# SCH_DART-Flight-Computer-5_2024-08-18.net
KiCad netlist of a schematic drawn in EasyEDA
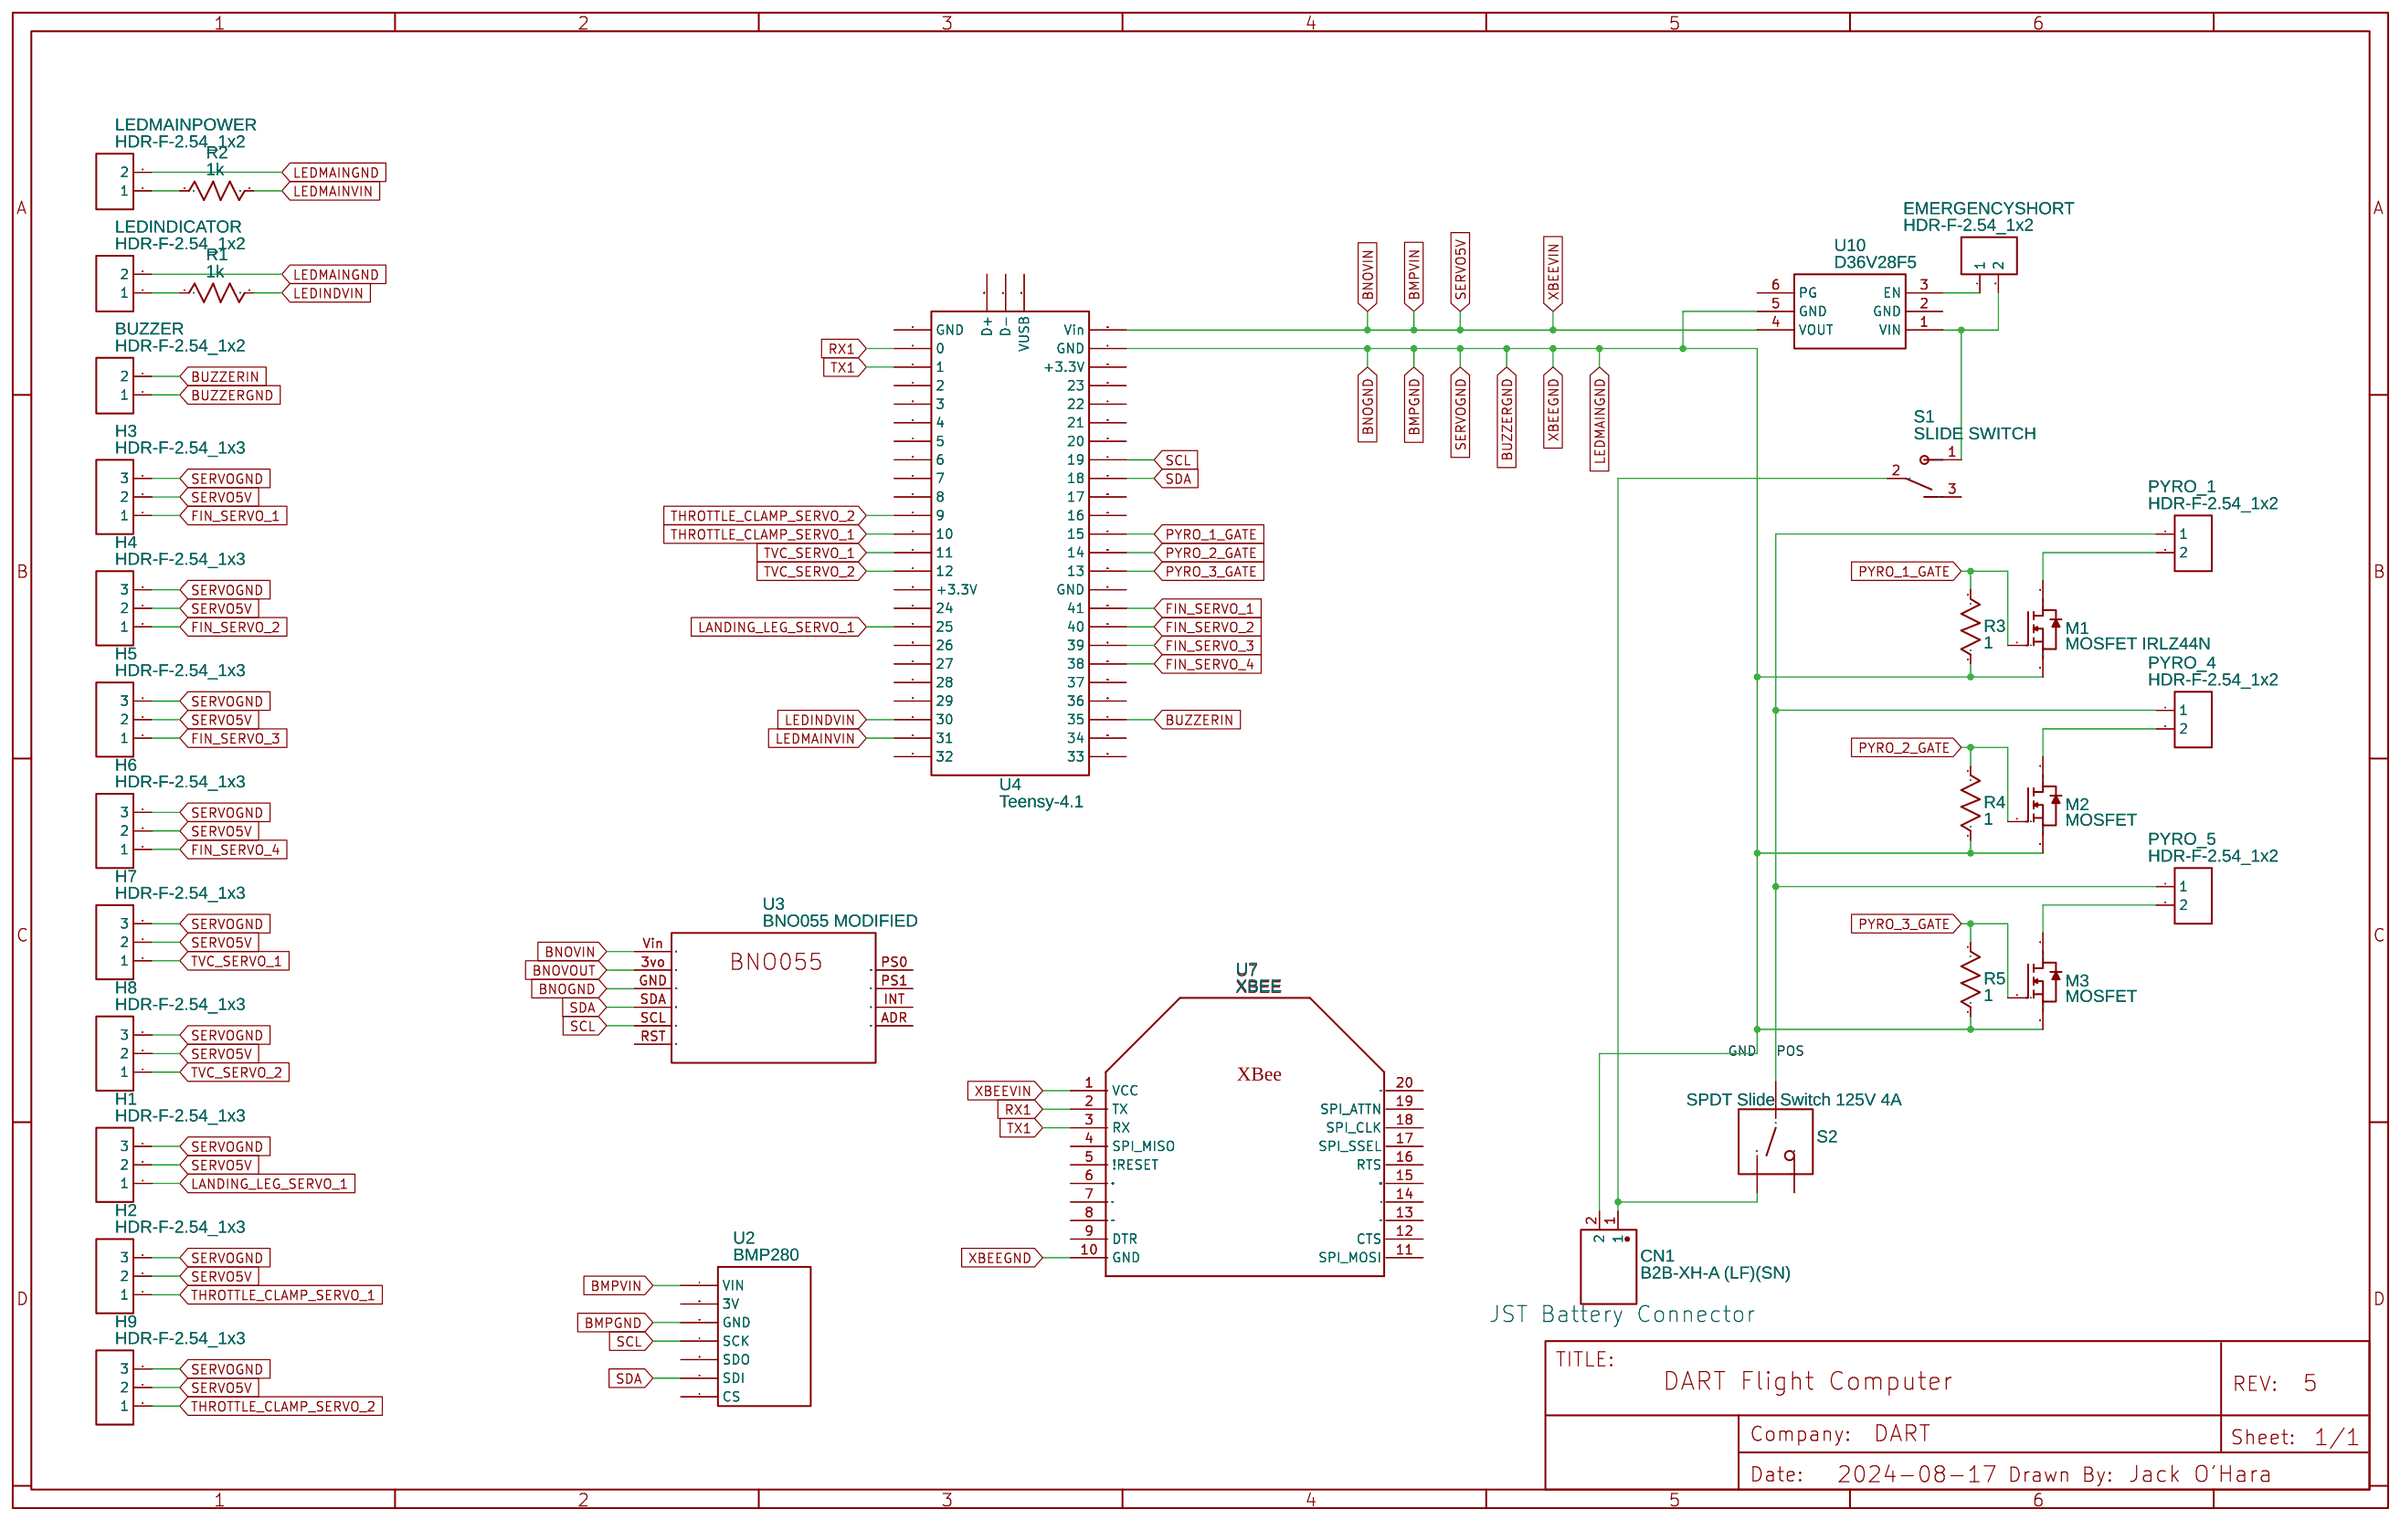
[diagram p0: schematic sheet]

(export (version "E")
  (design (tool "Eeschema 10.0.6"))
  (components
    (comp (ref "BUZZER") (value "HDR-F-2.54_1x2") (libsource (lib "") (part "HDR-F-2.54_1x2_4")))
    (comp (ref "CN1")
      (value "B2B-XH-A (LF)(SN)")
      (fields (field (name "Manufacturer Part") "B2B-XH-A(LF)(SN)") (field (name "Manufacturer") "JST"))
      (libsource (lib "") (part "B2B-XH-A (LF)(SN)"))
    )
    (comp (ref "EMERGENCYSHORT") (value "HDR-F-2.54_1x2") (libsource (lib "") (part "HDR-F-2.54_1x2_2")))
    (comp (ref "H1") (value "HDR-F-2.54_1x3") (libsource (lib "") (part "HDR-F-2.54_1x3")))
    (comp (ref "H2") (value "HDR-F-2.54_1x3") (libsource (lib "") (part "HDR-F-2.54_1x3")))
    (comp (ref "H3") (value "HDR-F-2.54_1x3") (libsource (lib "") (part "HDR-F-2.54_1x3")))
    (comp (ref "H4") (value "HDR-F-2.54_1x3") (libsource (lib "") (part "HDR-F-2.54_1x3")))
    (comp (ref "H5") (value "HDR-F-2.54_1x3") (libsource (lib "") (part "HDR-F-2.54_1x3")))
    (comp (ref "H6") (value "HDR-F-2.54_1x3") (libsource (lib "") (part "HDR-F-2.54_1x3")))
    (comp (ref "H7") (value "HDR-F-2.54_1x3") (libsource (lib "") (part "HDR-F-2.54_1x3")))
    (comp (ref "H8") (value "HDR-F-2.54_1x3") (libsource (lib "") (part "HDR-F-2.54_1x3")))
    (comp (ref "H9") (value "HDR-F-2.54_1x3") (libsource (lib "") (part "HDR-F-2.54_1x3")))
    (comp (ref "LEDINDICATOR") (value "HDR-F-2.54_1x2") (libsource (lib "") (part "HDR-F-2.54_1x2_3")))
    (comp (ref "LEDMAINPOWER") (value "HDR-F-2.54_1x2") (libsource (lib "") (part "HDR-F-2.54_1x2")))
    (comp (ref "M1") (value "MOSFET IRLZ44N") (libsource (lib "") (part "MOSFET")))
    (comp (ref "M2") (value "MOSFET") (libsource (lib "") (part "MOSFET")))
    (comp (ref "M3") (value "MOSFET") (libsource (lib "") (part "MOSFET")))
    (comp (ref "PYRO_1") (value "HDR-F-2.54_1x2") (libsource (lib "") (part "HDR-F-2.54_1x2_1")))
    (comp (ref "PYRO_4") (value "HDR-F-2.54_1x2") (libsource (lib "") (part "HDR-F-2.54_1x2_1")))
    (comp (ref "PYRO_5") (value "HDR-F-2.54_1x2") (libsource (lib "") (part "HDR-F-2.54_1x2_1")))
    (comp (ref "R1") (value "1k") (libsource (lib "") (part "R_0603_US")))
    (comp (ref "R2") (value "1k") (libsource (lib "") (part "R_0603_US")))
    (comp (ref "R3") (value "1") (libsource (lib "") (part "R_0603_US_1")))
    (comp (ref "R4") (value "1") (libsource (lib "") (part "R_0603_US_1")))
    (comp (ref "R5") (value "1") (libsource (lib "") (part "R_0603_US_1")))
    (comp (ref "S1") (value "SLIDE SWITCH") (libsource (lib "") (part "SLIDE SWITCH")))
    (comp (ref "S2")
      (value "SPDT Slide Switch 125V 4A")
      (fields
        (field (name "Manufacturer Part") "8SS1012-Z")
        (field (name "Manufacturer") "Nidec Copal Electronics")
      )
      (libsource (lib "") (part "SPDT Slide Switch 125V 4A"))
    )
    (comp (ref "U2") (value "BMP280") (libsource (lib "") (part "BMP280")))
    (comp (ref "U3") (value "BNO055 MODIFIED") (libsource (lib "") (part "BNO055 MODIFIED")))
    (comp (ref "U4") (value "Teensy-4.1") (libsource (lib "") (part "Teensy-4.1")))
    (comp (ref "U7") (value "XBEE") (libsource (lib "") (part "XBEE")))
    (comp (ref "U10")
      (value "D36V28F5")
      (fields
        (field (name "Manufacturer Part") "Pololu D36V28F5 Step-down regulator 5v fixed")
        (field (name "Manufacturer") "Pololu")
      )
      (libsource (lib "") (part "D36V28F5"))
    )
  )
  (nets
    (net (code "1") (name "/POS") (class "Default")
      (node (ref "PYRO_1") (pin "1") (pinfunction "1_1") (pintype "input"))
      (node (ref "PYRO_4") (pin "1") (pinfunction "1_1") (pintype "input"))
      (node (ref "PYRO_5") (pin "1") (pinfunction "1_1") (pintype "input"))
      (node (ref "S2") (pin "2") (pinfunction "2_2") (pintype "unspecified"))
    )
    (net (code "2") (name "BMPGND") (class "Default")
      (node (ref "BUZZER") (pin "1") (pinfunction "1_1") (pintype "input"))
      (node (ref "CN1") (pin "2") (pinfunction "2_2") (pintype "unspecified"))
      (node (ref "H1") (pin "3") (pinfunction "3_3") (pintype "input"))
      (node (ref "H2") (pin "3") (pinfunction "3_3") (pintype "input"))
      (node (ref "H3") (pin "3") (pinfunction "3_3") (pintype "input"))
      (node (ref "H4") (pin "3") (pinfunction "3_3") (pintype "input"))
      (node (ref "H5") (pin "3") (pinfunction "3_3") (pintype "input"))
      (node (ref "H6") (pin "3") (pinfunction "3_3") (pintype "input"))
      (node (ref "H7") (pin "3") (pinfunction "3_3") (pintype "input"))
      (node (ref "H8") (pin "3") (pinfunction "3_3") (pintype "input"))
      (node (ref "H9") (pin "3") (pinfunction "3_3") (pintype "input"))
      (node (ref "LEDINDICATOR") (pin "2") (pinfunction "2_2") (pintype "input"))
      (node (ref "LEDMAINPOWER") (pin "2") (pinfunction "2_2") (pintype "input"))
      (node (ref "M1") (pin "2") (pinfunction "2_2") (pintype "unspecified"))
      (node (ref "M2") (pin "2") (pinfunction "2_2") (pintype "unspecified"))
      (node (ref "M3") (pin "2") (pinfunction "2_2") (pintype "unspecified"))
      (node (ref "R3") (pin "1") (pinfunction "1_1") (pintype "unspecified"))
      (node (ref "R4") (pin "1") (pinfunction "1_1") (pintype "unspecified"))
      (node (ref "R5") (pin "1") (pinfunction "1_1") (pintype "unspecified"))
      (node (ref "U10") (pin "5") (pinfunction "GND_5") (pintype "unspecified"))
      (node (ref "U2") (pin "5") (pinfunction "GND_5") (pintype "unspecified"))
      (node (ref "U3") (pin "GND") (pinfunction "GND_GND") (pintype "unspecified"))
      (node (ref "U4") (pin "47") (pinfunction "GND_47") (pintype "unspecified"))
      (node (ref "U7") (pin "10") (pinfunction "GND_10") (pintype "unspecified"))
    )
    (net (code "3") (name "BMPVIN") (class "Default")
      (node (ref "H1") (pin "2") (pinfunction "2_2") (pintype "input"))
      (node (ref "H2") (pin "2") (pinfunction "2_2") (pintype "input"))
      (node (ref "H3") (pin "2") (pinfunction "2_2") (pintype "input"))
      (node (ref "H4") (pin "2") (pinfunction "2_2") (pintype "input"))
      (node (ref "H5") (pin "2") (pinfunction "2_2") (pintype "input"))
      (node (ref "H6") (pin "2") (pinfunction "2_2") (pintype "input"))
      (node (ref "H7") (pin "2") (pinfunction "2_2") (pintype "input"))
      (node (ref "H8") (pin "2") (pinfunction "2_2") (pintype "input"))
      (node (ref "H9") (pin "2") (pinfunction "2_2") (pintype "input"))
      (node (ref "U10") (pin "4") (pinfunction "VOUT_4") (pintype "unspecified"))
      (node (ref "U2") (pin "7") (pinfunction "VIN_7") (pintype "unspecified"))
      (node (ref "U3") (pin "Vin") (pinfunction "Vin_Vin") (pintype "unspecified"))
      (node (ref "U4") (pin "48") (pinfunction "Vin_48") (pintype "unspecified"))
      (node (ref "U7") (pin "1") (pinfunction "VCC_1") (pintype "unspecified"))
    )
    (net (code "4") (name "BNOVOUT") (class "Default")
      (node (ref "U3") (pin "3vo") (pinfunction "3vo_3vo") (pintype "unspecified"))
    )
    (net (code "5") (name "BUZZERIN") (class "Default")
      (node (ref "BUZZER") (pin "2") (pinfunction "2_2") (pintype "input"))
      (node (ref "U4") (pin "27") (pinfunction "35_27") (pintype "unspecified"))
    )
    (net (code "6") (name "FIN_SERVO_1") (class "Default")
      (node (ref "H3") (pin "1") (pinfunction "1_1") (pintype "input"))
      (node (ref "U4") (pin "33") (pinfunction "41_33") (pintype "unspecified"))
    )
    (net (code "7") (name "FIN_SERVO_2") (class "Default")
      (node (ref "H4") (pin "1") (pinfunction "1_1") (pintype "input"))
      (node (ref "U4") (pin "32") (pinfunction "40_32") (pintype "unspecified"))
    )
    (net (code "8") (name "FIN_SERVO_3") (class "Default")
      (node (ref "H5") (pin "1") (pinfunction "1_1") (pintype "input"))
      (node (ref "U4") (pin "31") (pinfunction "39_31") (pintype "unspecified"))
    )
    (net (code "9") (name "FIN_SERVO_4") (class "Default")
      (node (ref "H6") (pin "1") (pinfunction "1_1") (pintype "input"))
      (node (ref "U4") (pin "30") (pinfunction "38_30") (pintype "unspecified"))
    )
    (net (code "10") (name "LANDING_LEG_SERVO_1") (class "Default")
      (node (ref "H1") (pin "1") (pinfunction "1_1") (pintype "input"))
      (node (ref "U4") (pin "17") (pinfunction "25_17") (pintype "unspecified"))
    )
    (net (code "11") (name "LEDINDVIN") (class "Default")
      (node (ref "R1") (pin "2") (pinfunction "2_2") (pintype "unspecified"))
      (node (ref "U4") (pin "22") (pinfunction "30_22") (pintype "unspecified"))
    )
    (net (code "12") (name "LEDMAINVIN") (class "Default")
      (node (ref "R2") (pin "2") (pinfunction "2_2") (pintype "unspecified"))
      (node (ref "U4") (pin "23") (pinfunction "31_23") (pintype "unspecified"))
    )
    (net (code "13") (name "Net-(CN1-Pad1)") (class "Default")
      (node (ref "CN1") (pin "1") (pinfunction "1_1") (pintype "unspecified"))
      (node (ref "S1") (pin "2") (pinfunction "2_2") (pintype "bidirectional"))
      (node (ref "S2") (pin "3") (pinfunction "3_3") (pintype "unspecified"))
    )
    (net (code "14") (name "Net-(LEDINDICATOR-Pad1)") (class "Default")
      (node (ref "LEDINDICATOR") (pin "1") (pinfunction "1_1") (pintype "input"))
      (node (ref "R1") (pin "1") (pinfunction "1_1") (pintype "unspecified"))
    )
    (net (code "15") (name "Net-(LEDMAINPOWER-Pad1)") (class "Default")
      (node (ref "LEDMAINPOWER") (pin "1") (pinfunction "1_1") (pintype "input"))
      (node (ref "R2") (pin "1") (pinfunction "1_1") (pintype "unspecified"))
    )
    (net (code "16") (name "Net-(M1-Pad3)") (class "Default")
      (node (ref "M1") (pin "3") (pinfunction "3_3") (pintype "unspecified"))
      (node (ref "PYRO_1") (pin "2") (pinfunction "2_2") (pintype "input"))
    )
    (net (code "17") (name "Net-(M2-Pad3)") (class "Default")
      (node (ref "M2") (pin "3") (pinfunction "3_3") (pintype "unspecified"))
      (node (ref "PYRO_4") (pin "2") (pinfunction "2_2") (pintype "input"))
    )
    (net (code "18") (name "Net-(M3-Pad3)") (class "Default")
      (node (ref "M3") (pin "3") (pinfunction "3_3") (pintype "unspecified"))
      (node (ref "PYRO_5") (pin "2") (pinfunction "2_2") (pintype "input"))
    )
    (net (code "19") (name "Net-(U10-EN)") (class "Default")
      (node (ref "EMERGENCYSHORT") (pin "1") (pinfunction "1_1") (pintype "input"))
      (node (ref "U10") (pin "3") (pinfunction "EN_3") (pintype "unspecified"))
    )
    (net (code "20") (name "Net-(U10-VIN)") (class "Default")
      (node (ref "EMERGENCYSHORT") (pin "2") (pinfunction "2_2") (pintype "input"))
      (node (ref "S1") (pin "1") (pinfunction "1_1") (pintype "bidirectional"))
      (node (ref "U10") (pin "1") (pinfunction "VIN_1") (pintype "unspecified"))
    )
    (net (code "21") (name "PYRO_1_GATE") (class "Default")
      (node (ref "M1") (pin "1") (pinfunction "1_1") (pintype "unspecified"))
      (node (ref "R3") (pin "2") (pinfunction "2_2") (pintype "unspecified"))
      (node (ref "U4") (pin "37") (pinfunction "15_37") (pintype "unspecified"))
    )
    (net (code "22") (name "PYRO_2_GATE") (class "Default")
      (node (ref "M2") (pin "1") (pinfunction "1_1") (pintype "unspecified"))
      (node (ref "R4") (pin "2") (pinfunction "2_2") (pintype "unspecified"))
      (node (ref "U4") (pin "36") (pinfunction "14_36") (pintype "unspecified"))
    )
    (net (code "23") (name "PYRO_3_GATE") (class "Default")
      (node (ref "M3") (pin "1") (pinfunction "1_1") (pintype "unspecified"))
      (node (ref "R5") (pin "2") (pinfunction "2_2") (pintype "unspecified"))
      (node (ref "U4") (pin "35") (pinfunction "13_35") (pintype "unspecified"))
    )
    (net (code "24") (name "RX1") (class "Default")
      (node (ref "U4") (pin "2") (pinfunction "0_2") (pintype "unspecified"))
      (node (ref "U7") (pin "2") (pinfunction "TX_2") (pintype "output"))
    )
    (net (code "25") (name "SCL") (class "Default")
      (node (ref "U2") (pin "4") (pinfunction "SCK_4") (pintype "unspecified"))
      (node (ref "U3") (pin "SCL") (pinfunction "SCL_SCL") (pintype "unspecified"))
      (node (ref "U4") (pin "41") (pinfunction "19_41") (pintype "unspecified"))
    )
    (net (code "26") (name "SDA") (class "Default")
      (node (ref "U2") (pin "2") (pinfunction "SDI_2") (pintype "unspecified"))
      (node (ref "U3") (pin "SDA") (pinfunction "SDA_SDA") (pintype "unspecified"))
      (node (ref "U4") (pin "40") (pinfunction "18_40") (pintype "unspecified"))
    )
    (net (code "27") (name "THROTTLE_CLAMP_SERVO_1") (class "Default")
      (node (ref "H2") (pin "1") (pinfunction "1_1") (pintype "input"))
      (node (ref "U4") (pin "12") (pinfunction "10_12") (pintype "unspecified"))
    )
    (net (code "28") (name "THROTTLE_CLAMP_SERVO_2") (class "Default")
      (node (ref "H9") (pin "1") (pinfunction "1_1") (pintype "input"))
      (node (ref "U4") (pin "11") (pinfunction "9_11") (pintype "unspecified"))
    )
    (net (code "29") (name "TVC_SERVO_1") (class "Default")
      (node (ref "H7") (pin "1") (pinfunction "1_1") (pintype "input"))
      (node (ref "U4") (pin "13") (pinfunction "11_13") (pintype "unspecified"))
    )
    (net (code "30") (name "TVC_SERVO_2") (class "Default")
      (node (ref "H8") (pin "1") (pinfunction "1_1") (pintype "input"))
      (node (ref "U4") (pin "14") (pinfunction "12_14") (pintype "unspecified"))
    )
    (net (code "31") (name "TX1") (class "Default")
      (node (ref "U4") (pin "3") (pinfunction "1_3") (pintype "unspecified"))
      (node (ref "U7") (pin "3") (pinfunction "RX_3") (pintype "input"))
    )
    (net (code "32") (name "unconnected-(S1-Pad3)") (class "Default")
      (node (ref "S1") (pin "3") (pinfunction "3_3") (pintype "bidirectional"))
    )
    (net (code "33") (name "unconnected-(S2-Pad1)") (class "Default")
      (node (ref "S2") (pin "1") (pinfunction "1_1") (pintype "unspecified"))
    )
    (net (code "34") (name "unconnected-(U2-3V-Pad6)") (class "Default")
      (node (ref "U2") (pin "6") (pinfunction "3V_6") (pintype "unspecified"))
    )
    (net (code "35") (name "unconnected-(U2-CS-Pad1)") (class "Default")
      (node (ref "U2") (pin "1") (pinfunction "CS_1") (pintype "unspecified"))
    )
    (net (code "36") (name "unconnected-(U2-SDO-Pad3)") (class "Default")
      (node (ref "U2") (pin "3") (pinfunction "SDO_3") (pintype "unspecified"))
    )
    (net (code "37") (name "unconnected-(U3-PadADR)") (class "Default")
      (node (ref "U3") (pin "ADR") (pinfunction "ADR_ADR") (pintype "unspecified"))
    )
    (net (code "38") (name "unconnected-(U3-PadINT)") (class "Default")
      (node (ref "U3") (pin "INT") (pinfunction "INT_INT") (pintype "unspecified"))
    )
    (net (code "39") (name "unconnected-(U3-PadPS0)") (class "Default")
      (node (ref "U3") (pin "PS0") (pinfunction "PS0_PS0") (pintype "unspecified"))
    )
    (net (code "40") (name "unconnected-(U3-PadPS1)") (class "Default")
      (node (ref "U3") (pin "PS1") (pinfunction "PS1_PS1") (pintype "unspecified"))
    )
    (net (code "41") (name "unconnected-(U3-PadRST)") (class "Default")
      (node (ref "U3") (pin "RST") (pinfunction "RST_RST") (pintype "unspecified"))
    )
    (net (code "42") (name "unconnected-(U4-+3.3V-Pad15)") (class "Default")
      (node (ref "U4") (pin "15") (pinfunction "+3.3V_15") (pintype "unspecified"))
    )
    (net (code "43") (name "unconnected-(U4-+3.3V-Pad46)") (class "Default")
      (node (ref "U4") (pin "46") (pinfunction "+3.3V_46") (pintype "unspecified"))
    )
    (net (code "44") (name "unconnected-(U4-2-Pad4)") (class "Default")
      (node (ref "U4") (pin "4") (pinfunction "2_4") (pintype "unspecified"))
    )
    (net (code "45") (name "unconnected-(U4-3-Pad5)") (class "Default")
      (node (ref "U4") (pin "5") (pinfunction "3_5") (pintype "unspecified"))
    )
    (net (code "46") (name "unconnected-(U4-4-Pad6)") (class "Default")
      (node (ref "U4") (pin "6") (pinfunction "4_6") (pintype "unspecified"))
    )
    (net (code "47") (name "unconnected-(U4-5-Pad7)") (class "Default")
      (node (ref "U4") (pin "7") (pinfunction "5_7") (pintype "unspecified"))
    )
    (net (code "48") (name "unconnected-(U4-6-Pad8)") (class "Default")
      (node (ref "U4") (pin "8") (pinfunction "6_8") (pintype "unspecified"))
    )
    (net (code "49") (name "unconnected-(U4-7-Pad9)") (class "Default")
      (node (ref "U4") (pin "9") (pinfunction "7_9") (pintype "unspecified"))
    )
    (net (code "50") (name "unconnected-(U4-8-Pad10)") (class "Default")
      (node (ref "U4") (pin "10") (pinfunction "8_10") (pintype "unspecified"))
    )
    (net (code "51") (name "unconnected-(U4-16-Pad38)") (class "Default")
      (node (ref "U4") (pin "38") (pinfunction "16_38") (pintype "unspecified"))
    )
    (net (code "52") (name "unconnected-(U4-17-Pad39)") (class "Default")
      (node (ref "U4") (pin "39") (pinfunction "17_39") (pintype "unspecified"))
    )
    (net (code "53") (name "unconnected-(U4-20-Pad42)") (class "Default")
      (node (ref "U4") (pin "42") (pinfunction "20_42") (pintype "unspecified"))
    )
    (net (code "54") (name "unconnected-(U4-21-Pad43)") (class "Default")
      (node (ref "U4") (pin "43") (pinfunction "21_43") (pintype "unspecified"))
    )
    (net (code "55") (name "unconnected-(U4-22-Pad44)") (class "Default")
      (node (ref "U4") (pin "44") (pinfunction "22_44") (pintype "unspecified"))
    )
    (net (code "56") (name "unconnected-(U4-23-Pad45)") (class "Default")
      (node (ref "U4") (pin "45") (pinfunction "23_45") (pintype "unspecified"))
    )
    (net (code "57") (name "unconnected-(U4-24-Pad16)") (class "Default")
      (node (ref "U4") (pin "16") (pinfunction "24_16") (pintype "unspecified"))
    )
    (net (code "58") (name "unconnected-(U4-26-Pad18)") (class "Default")
      (node (ref "U4") (pin "18") (pinfunction "26_18") (pintype "unspecified"))
    )
    (net (code "59") (name "unconnected-(U4-27-Pad19)") (class "Default")
      (node (ref "U4") (pin "19") (pinfunction "27_19") (pintype "unspecified"))
    )
    (net (code "60") (name "unconnected-(U4-28-Pad20)") (class "Default")
      (node (ref "U4") (pin "20") (pinfunction "28_20") (pintype "unspecified"))
    )
    (net (code "61") (name "unconnected-(U4-29-Pad21)") (class "Default")
      (node (ref "U4") (pin "21") (pinfunction "29_21") (pintype "unspecified"))
    )
    (net (code "62") (name "unconnected-(U4-32-Pad24)") (class "Default")
      (node (ref "U4") (pin "24") (pinfunction "32_24") (pintype "unspecified"))
    )
    (net (code "63") (name "unconnected-(U4-33-Pad25)") (class "Default")
      (node (ref "U4") (pin "25") (pinfunction "33_25") (pintype "unspecified"))
    )
    (net (code "64") (name "unconnected-(U4-34-Pad26)") (class "Default")
      (node (ref "U4") (pin "26") (pinfunction "34_26") (pintype "unspecified"))
    )
    (net (code "65") (name "unconnected-(U4-36-Pad28)") (class "Default")
      (node (ref "U4") (pin "28") (pinfunction "36_28") (pintype "unspecified"))
    )
    (net (code "66") (name "unconnected-(U4-37-Pad29)") (class "Default")
      (node (ref "U4") (pin "29") (pinfunction "37_29") (pintype "unspecified"))
    )
    (net (code "67") (name "unconnected-(U4-D+-Pad66)") (class "Default")
      (node (ref "U4") (pin "66") (pinfunction "D+_66") (pintype "unspecified"))
    )
    (net (code "68") (name "unconnected-(U4-D--Pad67)") (class "Default")
      (node (ref "U4") (pin "67") (pinfunction "D-_67") (pintype "unspecified"))
    )
    (net (code "69") (name "unconnected-(U4-GND-Pad1)") (class "Default")
      (node (ref "U4") (pin "1") (pinfunction "GND_1") (pintype "unspecified"))
    )
    (net (code "70") (name "unconnected-(U4-GND-Pad34)") (class "Default")
      (node (ref "U4") (pin "34") (pinfunction "GND_34") (pintype "unspecified"))
    )
    (net (code "71") (name "unconnected-(U4-VUSB-Pad52)") (class "Default")
      (node (ref "U4") (pin "52") (pinfunction "VUSB_52") (pintype "unspecified"))
    )
    (net (code "72") (name "unconnected-(U7-!RESET-Pad5)") (class "Default")
      (node (ref "U7") (pin "5") (pinfunction "!RESET_5") (pintype "input"))
    )
    (net (code "73") (name "unconnected-(U7-AD0DIO0-Pad20)") (class "Default")
      (node (ref "U7") (pin "20") (pinfunction "AD0DIO0_20") (pintype "unspecified"))
    )
    (net (code "74") (name "unconnected-(U7-ASCAD5DIO5-Pad15)") (class "Default")
      (node (ref "U7") (pin "15") (pinfunction "ASCAD5DIO5_15") (pintype "unspecified"))
    )
    (net (code "75") (name "unconnected-(U7-CTS-Pad12)") (class "Default")
      (node (ref "U7") (pin "12") (pinfunction "CTS_12") (pintype "unspecified"))
    )
    (net (code "76") (name "unconnected-(U7-DTR-Pad9)") (class "Default")
      (node (ref "U7") (pin "9") (pinfunction "DTR_9") (pintype "unspecified"))
    )
    (net (code "77") (name "unconnected-(U7-ONSLEEP-Pad13)") (class "Default")
      (node (ref "U7") (pin "13") (pinfunction "ONSLEEP_13") (pintype "output"))
    )
    (net (code "78") (name "unconnected-(U7-PWM0RSSI-Pad6)") (class "Default")
      (node (ref "U7") (pin "6") (pinfunction "PWM0RSSI_6") (pintype "output"))
    )
    (net (code "79") (name "unconnected-(U7-PWM1-Pad7)") (class "Default")
      (node (ref "U7") (pin "7") (pinfunction "PWM1_7") (pintype "output"))
    )
    (net (code "80") (name "unconnected-(U7-RESERVED-Pad8)") (class "Default")
      (node (ref "U7") (pin "8") (pinfunction "RESERVED_8") (pintype "unspecified"))
    )
    (net (code "81") (name "unconnected-(U7-RTS-Pad16)") (class "Default")
      (node (ref "U7") (pin "16") (pinfunction "RTS_16") (pintype "unspecified"))
    )
    (net (code "82") (name "unconnected-(U7-SPI_ATTN-Pad19)") (class "Default")
      (node (ref "U7") (pin "19") (pinfunction "SPI_ATTN_19") (pintype "unspecified"))
    )
    (net (code "83") (name "unconnected-(U7-SPI_CLK-Pad18)") (class "Default")
      (node (ref "U7") (pin "18") (pinfunction "SPI_CLK_18") (pintype "unspecified"))
    )
    (net (code "84") (name "unconnected-(U7-SPI_MISO-Pad4)") (class "Default")
      (node (ref "U7") (pin "4") (pinfunction "SPI_MISO_4") (pintype "output"))
    )
    (net (code "85") (name "unconnected-(U7-SPI_MOSI-Pad11)") (class "Default")
      (node (ref "U7") (pin "11") (pinfunction "SPI_MOSI_11") (pintype "unspecified"))
    )
    (net (code "86") (name "unconnected-(U7-SPI_SSEL-Pad17)") (class "Default")
      (node (ref "U7") (pin "17") (pinfunction "SPI_SSEL_17") (pintype "unspecified"))
    )
    (net (code "87") (name "unconnected-(U7-VREF-Pad14)") (class "Default")
      (node (ref "U7") (pin "14") (pinfunction "VREF_14") (pintype "input"))
    )
    (net (code "88") (name "unconnected-(U10-GND-Pad2)") (class "Default")
      (node (ref "U10") (pin "2") (pinfunction "GND_2") (pintype "unspecified"))
    )
    (net (code "89") (name "unconnected-(U10-PG-Pad6)") (class "Default")
      (node (ref "U10") (pin "6") (pinfunction "PG_6") (pintype "unspecified"))
    )
  )
)
